# Walking_analysis_design.net
KiCad netlist of a schematic drawn in EAGLE
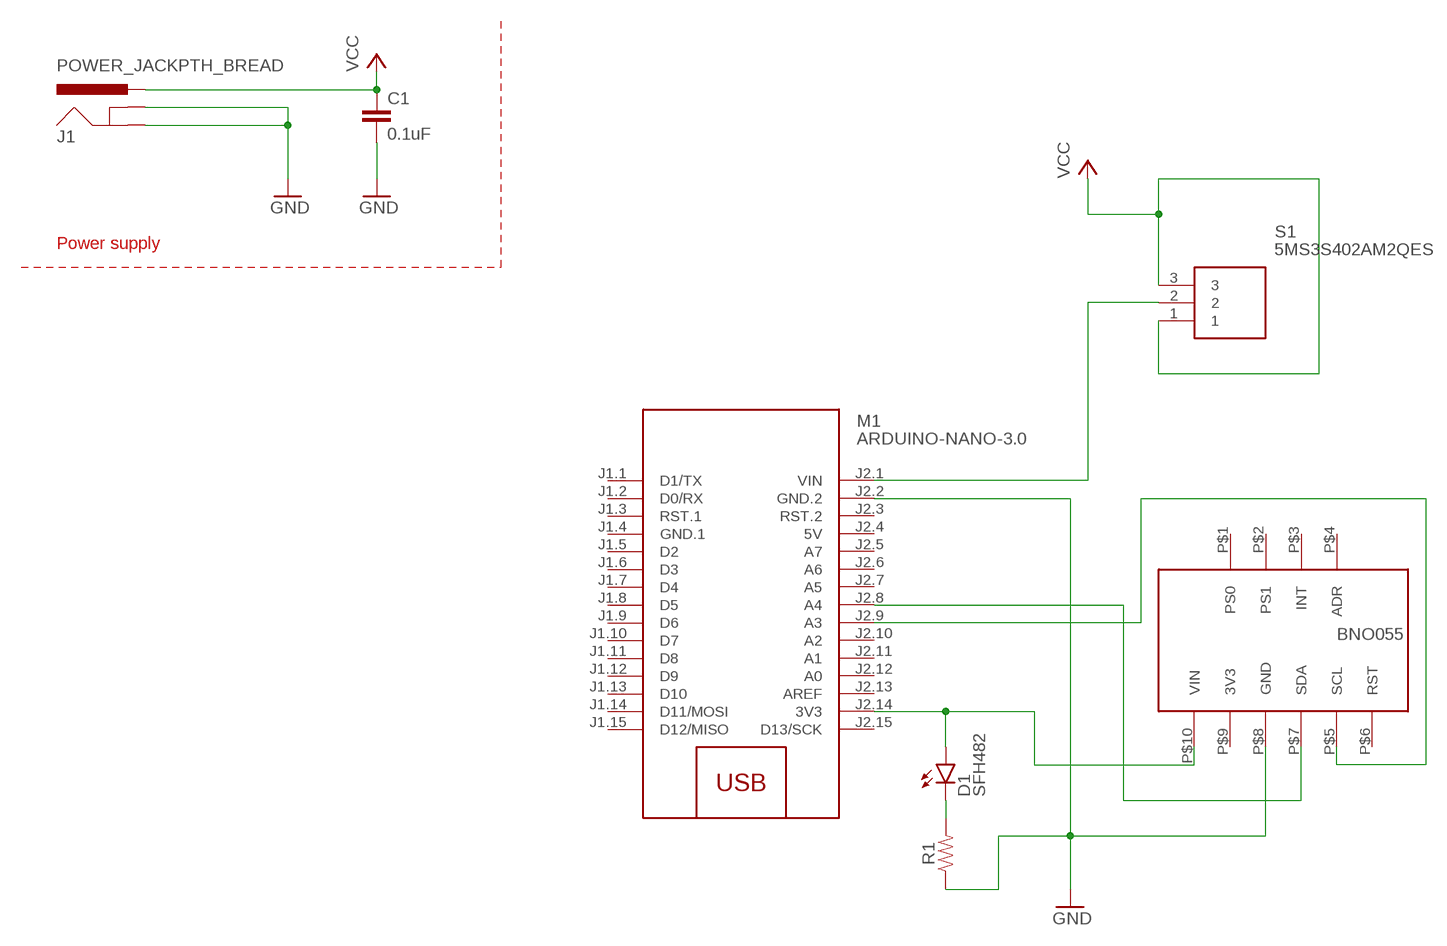
[diagram p0: schematic, sheet 1]

(export (version "E")
  (design (tool "Eeschema 10.0.6"))
  (components
    (comp (ref "C1")
      (value "0.1uF")
      (footprint "eagle-import:CAP-PTH-SMALL-KIT")
      (libsource (lib "eagle-import") (part "0.1UF-KIT-EZ-50V-20%"))
    )
    (comp (ref "D1")
      (value "SFH482")
      (footprint "eagle-import:SFH482")
      (libsource (lib "eagle-import") (part "SFH482"))
    )
    (comp (ref "J1")
      (value "POWER_JACKPTH_BREAD")
      (footprint "eagle-import:POWER_JACK_PTH_BREAD")
      (libsource (lib "eagle-import") (part "POWER_JACKPTH_BREAD"))
    )
    (comp (ref "M1")
      (value "ARDUINO-NANO-3.0")
      (footprint "eagle-import:ARDUINO-NANO-3.0")
      (libsource (lib "eagle-import") (part "ARDUINO-NANO-3.0"))
    )
    (comp (ref "R1")
      (value "RESISTORAXIAL-0.3")
      (footprint "eagle-import:AXIAL-0.3")
      (libsource (lib "eagle-import") (part "RESISTORAXIAL-0.3"))
    )
    (comp (ref "S1")
      (value "5MS3S402AM2QES")
      (footprint "eagle-import:5MS3S402AM2QES")
      (fields (field (name "RS_PART_NUMBER") "7347334"))
      (libsource (lib "eagle-import") (part "5MS3S402AM2QES"))
    )
    (comp (ref "U$1")
      (value "BNO055")
      (footprint "eagle-import:BNO055_FOOTPRINT")
      (libsource (lib "eagle-import") (part "BNO055"))
    )
  )
  (nets
    (net (code "1") (name "/3V3") (class "Default")
      (node (ref "U$1") (pin "P$9") (pinfunction "3V3_P$9") (pintype "power_in"))
    )
    (net (code "2") (name "/5V") (class "Default")
      (node (ref "M1") (pin "J2.4") (pinfunction "5V_J2.4") (pintype "power_in"))
    )
    (net (code "3") (name "/GND.1") (class "Default")
      (node (ref "M1") (pin "J1.4") (pinfunction "GND.1_J1.4") (pintype "power_in"))
    )
    (net (code "4") (name "GND") (class "Default")
      (node (ref "C1") (pin "2") (pinfunction "2_2") (pintype "passive"))
      (node (ref "J1") (pin "GND") (pinfunction "GND_GND") (pintype "bidirectional"))
      (node (ref "J1") (pin "GNDBREAK") (pinfunction "GNDBREAK_GNDBREAK") (pintype "bidirectional"))
      (node (ref "M1") (pin "J2.2") (pinfunction "GND.2_J2.2") (pintype "power_in"))
      (node (ref "R1") (pin "P$1") (pinfunction "1_P$1") (pintype "passive"))
      (node (ref "U$1") (pin "P$8") (pinfunction "GND_P$8") (pintype "power_in"))
    )
    (net (code "5") (name "Net-(D1-C)") (class "Default")
      (node (ref "D1") (pin "K") (pinfunction "C_K") (pintype "passive"))
      (node (ref "R1") (pin "P$2") (pinfunction "2_P$2") (pintype "passive"))
    )
    (net (code "6") (name "Net-(M1-3V3)") (class "Default")
      (node (ref "D1") (pin "A") (pinfunction "A_A") (pintype "passive"))
      (node (ref "M1") (pin "J2.14") (pinfunction "3V3_J2.14") (pintype "power_in"))
      (node (ref "U$1") (pin "P$10") (pinfunction "VIN_P$10") (pintype "power_in"))
    )
    (net (code "7") (name "Net-(M1-A3)") (class "Default")
      (node (ref "M1") (pin "J2.9") (pinfunction "A3_J2.9") (pintype "bidirectional"))
      (node (ref "U$1") (pin "P$5") (pinfunction "SCL_P$5") (pintype "bidirectional"))
    )
    (net (code "8") (name "Net-(M1-A4)") (class "Default")
      (node (ref "M1") (pin "J2.8") (pinfunction "A4_J2.8") (pintype "bidirectional"))
      (node (ref "U$1") (pin "P$7") (pinfunction "SDA_P$7") (pintype "bidirectional"))
    )
    (net (code "9") (name "Net-(M1-VIN)") (class "Default")
      (node (ref "M1") (pin "J2.1") (pinfunction "VIN_J2.1") (pintype "power_in"))
      (node (ref "S1") (pin "2") (pinfunction "2_2") (pintype "bidirectional"))
    )
    (net (code "10") (name "VCC") (class "Default")
      (node (ref "C1") (pin "1") (pinfunction "1_1") (pintype "passive"))
      (node (ref "J1") (pin "PWR") (pinfunction "PWR_PWR") (pintype "bidirectional"))
      (node (ref "S1") (pin "1") (pinfunction "1_1") (pintype "bidirectional"))
      (node (ref "S1") (pin "3") (pinfunction "3_3") (pintype "bidirectional"))
    )
    (net (code "11") (name "unconnected-(M1-A0-PadJ2.12)") (class "Default")
      (node (ref "M1") (pin "J2.12") (pinfunction "A0_J2.12") (pintype "bidirectional"))
    )
    (net (code "12") (name "unconnected-(M1-A1-PadJ2.11)") (class "Default")
      (node (ref "M1") (pin "J2.11") (pinfunction "A1_J2.11") (pintype "bidirectional"))
    )
    (net (code "13") (name "unconnected-(M1-A2-PadJ2.10)") (class "Default")
      (node (ref "M1") (pin "J2.10") (pinfunction "A2_J2.10") (pintype "bidirectional"))
    )
    (net (code "14") (name "unconnected-(M1-A5-PadJ2.7)") (class "Default")
      (node (ref "M1") (pin "J2.7") (pinfunction "A5_J2.7") (pintype "bidirectional"))
    )
    (net (code "15") (name "unconnected-(M1-A6-PadJ2.6)") (class "Default")
      (node (ref "M1") (pin "J2.6") (pinfunction "A6_J2.6") (pintype "bidirectional"))
    )
    (net (code "16") (name "unconnected-(M1-A7-PadJ2.5)") (class "Default")
      (node (ref "M1") (pin "J2.5") (pinfunction "A7_J2.5") (pintype "bidirectional"))
    )
    (net (code "17") (name "unconnected-(M1-AREF-PadJ2.13)") (class "Default")
      (node (ref "M1") (pin "J2.13") (pinfunction "AREF_J2.13") (pintype "bidirectional"))
    )
    (net (code "18") (name "unconnected-(M1-D0{slash}RX-PadJ1.2)") (class "Default")
      (node (ref "M1") (pin "J1.2") (pinfunction "D0/RX_J1.2") (pintype "bidirectional"))
    )
    (net (code "19") (name "unconnected-(M1-D1{slash}TX-PadJ1.1)") (class "Default")
      (node (ref "M1") (pin "J1.1") (pinfunction "D1/TX_J1.1") (pintype "bidirectional"))
    )
    (net (code "20") (name "unconnected-(M1-D2-PadJ1.5)") (class "Default")
      (node (ref "M1") (pin "J1.5") (pinfunction "D2_J1.5") (pintype "bidirectional"))
    )
    (net (code "21") (name "unconnected-(M1-D3-PadJ1.6)") (class "Default")
      (node (ref "M1") (pin "J1.6") (pinfunction "D3_J1.6") (pintype "bidirectional"))
    )
    (net (code "22") (name "unconnected-(M1-D4-PadJ1.7)") (class "Default")
      (node (ref "M1") (pin "J1.7") (pinfunction "D4_J1.7") (pintype "bidirectional"))
    )
    (net (code "23") (name "unconnected-(M1-D5-PadJ1.8)") (class "Default")
      (node (ref "M1") (pin "J1.8") (pinfunction "D5_J1.8") (pintype "bidirectional"))
    )
    (net (code "24") (name "unconnected-(M1-D6-PadJ1.9)") (class "Default")
      (node (ref "M1") (pin "J1.9") (pinfunction "D6_J1.9") (pintype "bidirectional"))
    )
    (net (code "25") (name "unconnected-(M1-D7-PadJ1.10)") (class "Default")
      (node (ref "M1") (pin "J1.10") (pinfunction "D7_J1.10") (pintype "bidirectional"))
    )
    (net (code "26") (name "unconnected-(M1-D8-PadJ1.11)") (class "Default")
      (node (ref "M1") (pin "J1.11") (pinfunction "D8_J1.11") (pintype "bidirectional"))
    )
    (net (code "27") (name "unconnected-(M1-D9-PadJ1.12)") (class "Default")
      (node (ref "M1") (pin "J1.12") (pinfunction "D9_J1.12") (pintype "bidirectional"))
    )
    (net (code "28") (name "unconnected-(M1-D10-PadJ1.13)") (class "Default")
      (node (ref "M1") (pin "J1.13") (pinfunction "D10_J1.13") (pintype "bidirectional"))
    )
    (net (code "29") (name "unconnected-(M1-D11{slash}MOSI-PadJ1.14)") (class "Default")
      (node (ref "M1") (pin "J1.14") (pinfunction "D11/MOSI_J1.14") (pintype "bidirectional"))
    )
    (net (code "30") (name "unconnected-(M1-D12{slash}MISO-PadJ1.15)") (class "Default")
      (node (ref "M1") (pin "J1.15") (pinfunction "D12/MISO_J1.15") (pintype "bidirectional"))
    )
    (net (code "31") (name "unconnected-(M1-D13{slash}SCK-PadJ2.15)") (class "Default")
      (node (ref "M1") (pin "J2.15") (pinfunction "D13/SCK_J2.15") (pintype "bidirectional"))
    )
    (net (code "32") (name "unconnected-(M1-RST.1-PadJ1.3)") (class "Default")
      (node (ref "M1") (pin "J1.3") (pinfunction "RST.1_J1.3") (pintype "bidirectional"))
    )
    (net (code "33") (name "unconnected-(M1-RST.2-PadJ2.3)") (class "Default")
      (node (ref "M1") (pin "J2.3") (pinfunction "RST.2_J2.3") (pintype "bidirectional"))
    )
    (net (code "34") (name "unconnected-(U$1-ADR-PadP$4)") (class "Default")
      (node (ref "U$1") (pin "P$4") (pinfunction "ADR_P$4") (pintype "bidirectional"))
    )
    (net (code "35") (name "unconnected-(U$1-INT-PadP$3)") (class "Default")
      (node (ref "U$1") (pin "P$3") (pinfunction "INT_P$3") (pintype "bidirectional"))
    )
    (net (code "36") (name "unconnected-(U$1-PS0-PadP$1)") (class "Default")
      (node (ref "U$1") (pin "P$1") (pinfunction "PS0_P$1") (pintype "bidirectional"))
    )
    (net (code "37") (name "unconnected-(U$1-PS1-PadP$2)") (class "Default")
      (node (ref "U$1") (pin "P$2") (pinfunction "PS1_P$2") (pintype "bidirectional"))
    )
    (net (code "38") (name "unconnected-(U$1-RST-PadP$6)") (class "Default")
      (node (ref "U$1") (pin "P$6") (pinfunction "RST_P$6") (pintype "bidirectional"))
    )
  )
)
